# blip.net
KiCad netlist of a schematic drawn in EAGLE
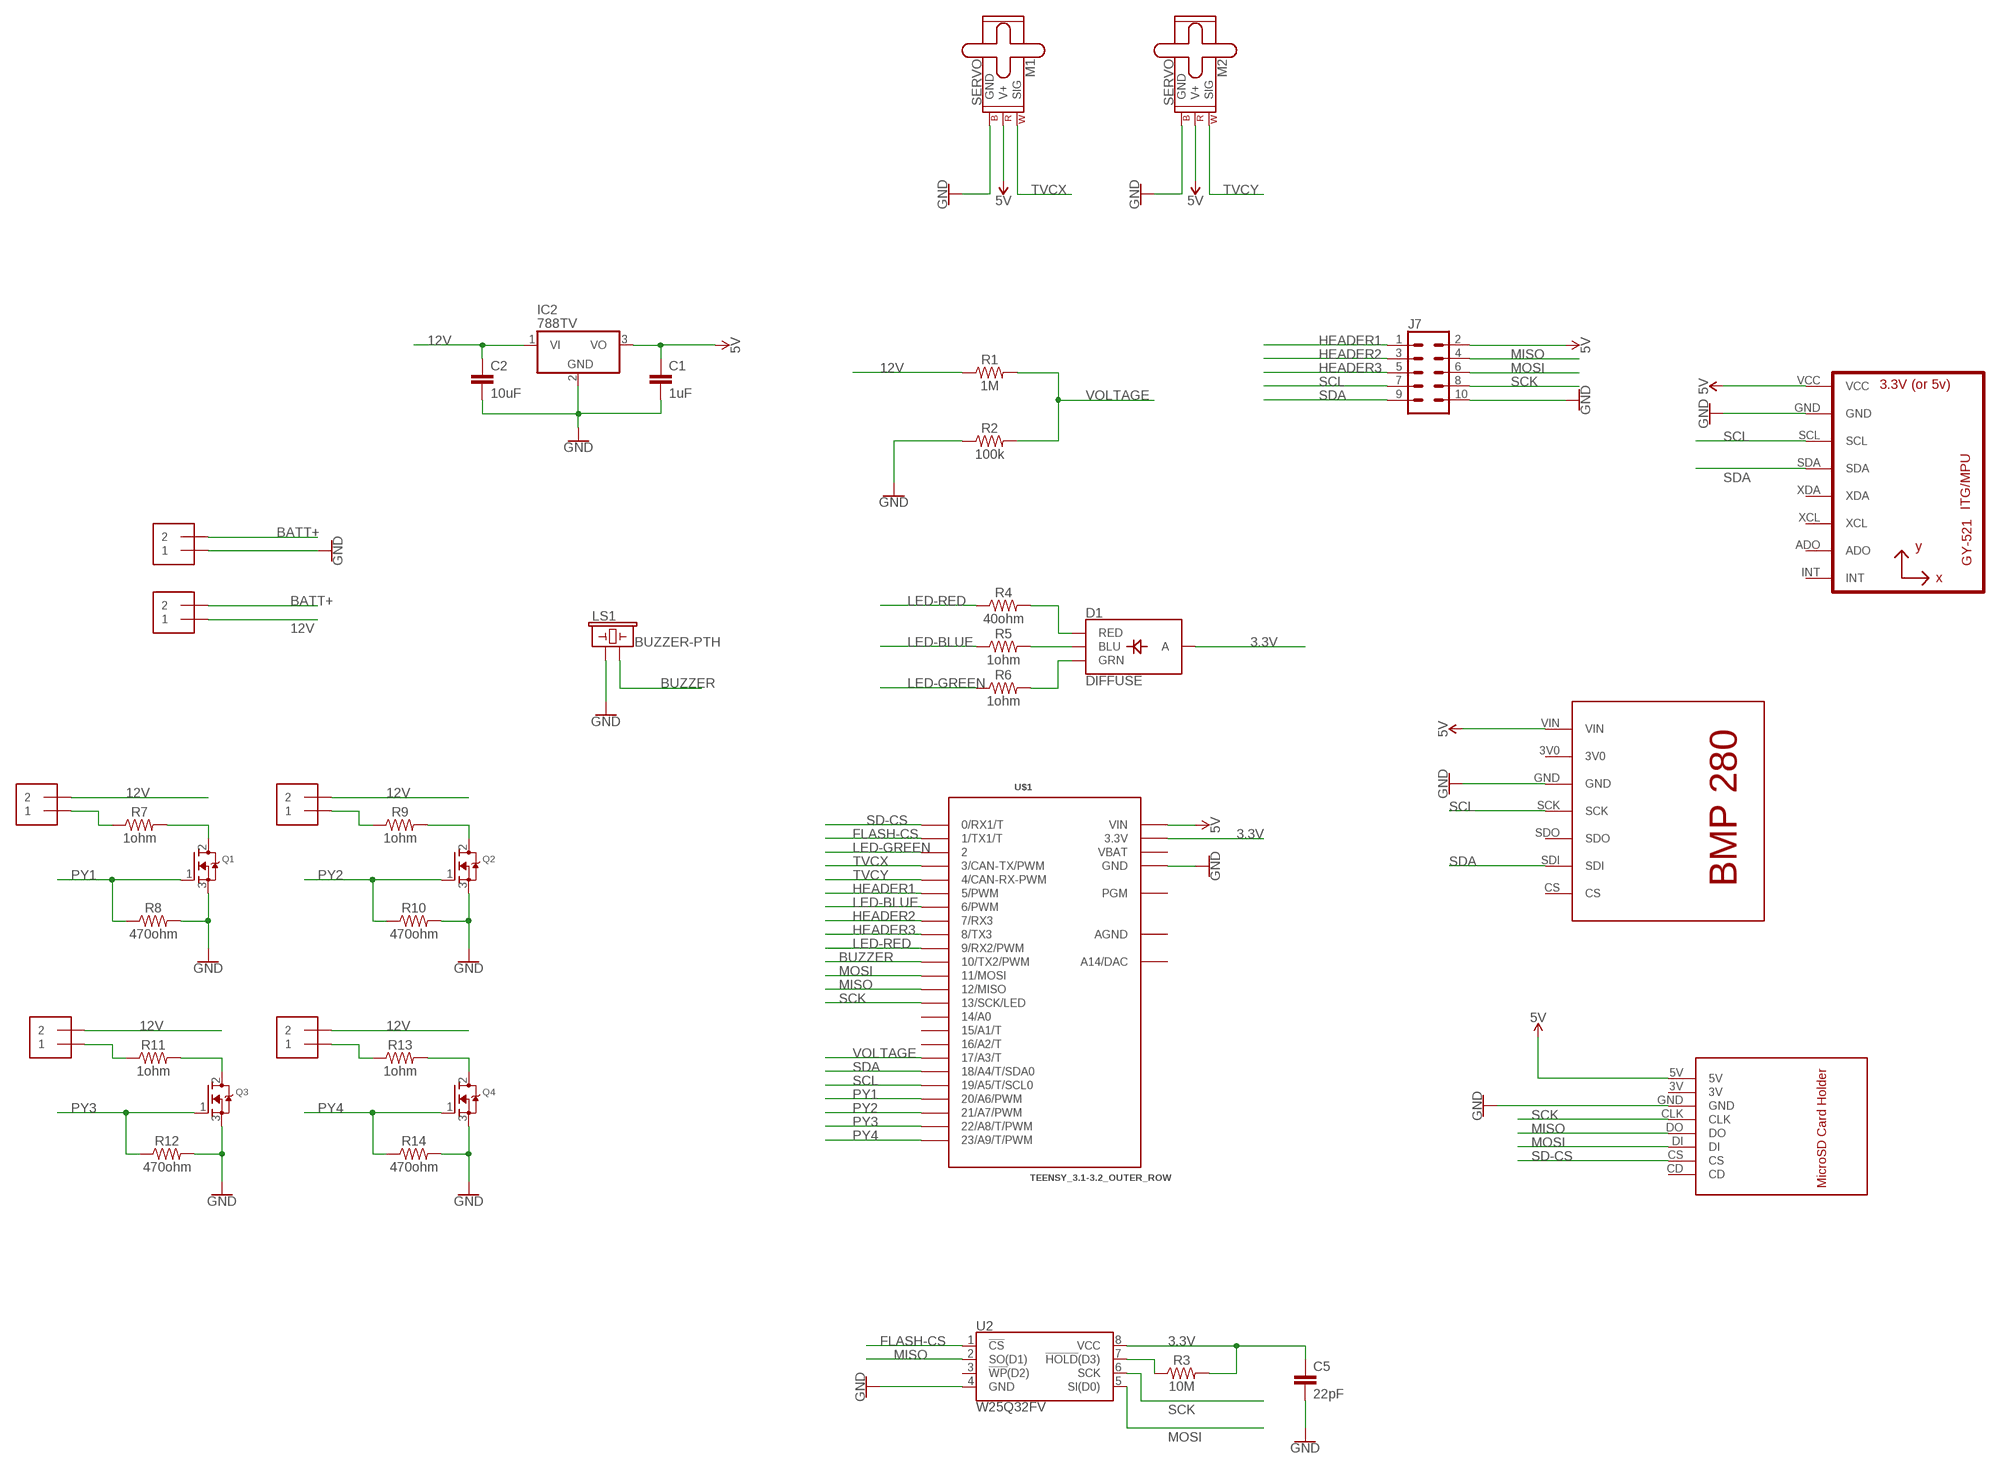
[diagram p0: schematic, sheet 1]

(export (version "E")
  (design (tool "Eeschema 10.0.6"))
  (components
    (comp (ref "C1")
      (value "1uF")
      (footprint "eagle-import:CAP-PTH-2.54")
      (libsource (lib "eagle-import") (part "22PF-PTH-2.54MM-200V-5%"))
    )
    (comp (ref "C2")
      (value "10uF")
      (footprint "eagle-import:CAP-PTH-2.54")
      (libsource (lib "eagle-import") (part "22PF-PTH-2.54MM-200V-5%"))
    )
    (comp (ref "C5")
      (value "22pF")
      (footprint "eagle-import:CAP-PTH-2.54")
      (libsource (lib "eagle-import") (part "22PF-PTH-2.54MM-200V-5%"))
    )
    (comp (ref "D1")
      (value "DIFFUSE")
      (footprint "eagle-import:LED-RGB-THRU")
      (libsource (lib "eagle-import") (part "LED-RGB-CADIFFUSE"))
    )
    (comp (ref "IC2")
      (value "788TV")
      (footprint "eagle-import:TO220V")
      (libsource (lib "eagle-import") (part "78TV8"))
    )
    (comp (ref "J1")
      (value "1X2-3.5MM")
      (footprint "eagle-import:1X2-3.5MM")
      (libsource (lib "eagle-import") (part "1X2-3.5MM"))
    )
    (comp (ref "J2")
      (value "1X2-3.5MM")
      (footprint "eagle-import:1X2-3.5MM")
      (libsource (lib "eagle-import") (part "1X2-3.5MM"))
    )
    (comp (ref "J3")
      (value "1X2-3.5MM")
      (footprint "eagle-import:1X2-3.5MM")
      (libsource (lib "eagle-import") (part "1X2-3.5MM"))
    )
    (comp (ref "J4")
      (value "1X2-3.5MM")
      (footprint "eagle-import:1X2-3.5MM")
      (libsource (lib "eagle-import") (part "1X2-3.5MM"))
    )
    (comp (ref "J5")
      (value "1X2-3.5MM")
      (footprint "eagle-import:1X2-3.5MM")
      (libsource (lib "eagle-import") (part "1X2-3.5MM"))
    )
    (comp (ref "J6")
      (value "1X2-3.5MM")
      (footprint "eagle-import:1X2-3.5MM")
      (libsource (lib "eagle-import") (part "1X2-3.5MM"))
    )
    (comp (ref "J7")
      (value "CONN_05X2NO_SILK")
      (footprint "eagle-import:2X5_NOSILK")
      (libsource (lib "eagle-import") (part "CONN_05X2NO_SILK"))
    )
    (comp (ref "LS1")
      (value "BUZZER-PTH")
      (footprint "eagle-import:BUZZER-12MM")
      (libsource (lib "eagle-import") (part "BUZZER-PTH"))
    )
    (comp (ref "M1")
      (value "SERVO")
      (footprint "eagle-import:1X03")
      (libsource (lib "eagle-import") (part "SERVO"))
    )
    (comp (ref "M2")
      (value "SERVO")
      (footprint "eagle-import:1X03")
      (libsource (lib "eagle-import") (part "SERVO"))
    )
    (comp (ref "Q1")
      (value "MOSFET-NGDS_TO220V")
      (footprint "eagle-import:TO220V")
      (libsource (lib "eagle-import") (part "MOSFET-NGDS_TO220V"))
    )
    (comp (ref "Q2")
      (value "MOSFET-NGDS_TO220V")
      (footprint "eagle-import:TO220V")
      (libsource (lib "eagle-import") (part "MOSFET-NGDS_TO220V"))
    )
    (comp (ref "Q3")
      (value "MOSFET-NGDS_TO220V")
      (footprint "eagle-import:TO220V")
      (libsource (lib "eagle-import") (part "MOSFET-NGDS_TO220V"))
    )
    (comp (ref "Q4")
      (value "MOSFET-NGDS_TO220V")
      (footprint "eagle-import:TO220V")
      (libsource (lib "eagle-import") (part "MOSFET-NGDS_TO220V"))
    )
    (comp (ref "R1")
      (value "1M")
      (footprint "eagle-import:AXIAL-0.3")
      (libsource (lib "eagle-import") (part "10MOHM-HORIZ-1/4W-5%"))
    )
    (comp (ref "R2")
      (value "100k")
      (footprint "eagle-import:AXIAL-0.3")
      (libsource (lib "eagle-import") (part "10MOHM-HORIZ-1/4W-5%"))
    )
    (comp (ref "R3")
      (value "10M")
      (footprint "eagle-import:AXIAL-0.3")
      (libsource (lib "eagle-import") (part "10MOHM-HORIZ-1/4W-5%"))
    )
    (comp (ref "R4")
      (value "40ohm")
      (footprint "eagle-import:AXIAL-0.3")
      (libsource (lib "eagle-import") (part "10MOHM-HORIZ-1/4W-5%"))
    )
    (comp (ref "R5")
      (value "1ohm")
      (footprint "eagle-import:AXIAL-0.3")
      (libsource (lib "eagle-import") (part "10MOHM-HORIZ-1/4W-5%"))
    )
    (comp (ref "R6")
      (value "1ohm")
      (footprint "eagle-import:AXIAL-0.3")
      (libsource (lib "eagle-import") (part "10MOHM-HORIZ-1/4W-5%"))
    )
    (comp (ref "R7")
      (value "1ohm")
      (footprint "eagle-import:AXIAL-0.3")
      (libsource (lib "eagle-import") (part "10MOHM-HORIZ-1/4W-5%"))
    )
    (comp (ref "R8")
      (value "470ohm")
      (footprint "eagle-import:AXIAL-0.3")
      (libsource (lib "eagle-import") (part "10MOHM-HORIZ-1/4W-5%"))
    )
    (comp (ref "R9")
      (value "1ohm")
      (footprint "eagle-import:AXIAL-0.3")
      (libsource (lib "eagle-import") (part "10MOHM-HORIZ-1/4W-5%"))
    )
    (comp (ref "R10")
      (value "470ohm")
      (footprint "eagle-import:AXIAL-0.3")
      (libsource (lib "eagle-import") (part "10MOHM-HORIZ-1/4W-5%"))
    )
    (comp (ref "R11")
      (value "1ohm")
      (footprint "eagle-import:AXIAL-0.3")
      (libsource (lib "eagle-import") (part "10MOHM-HORIZ-1/4W-5%"))
    )
    (comp (ref "R12")
      (value "470ohm")
      (footprint "eagle-import:AXIAL-0.3")
      (libsource (lib "eagle-import") (part "10MOHM-HORIZ-1/4W-5%"))
    )
    (comp (ref "R13")
      (value "1ohm")
      (footprint "eagle-import:AXIAL-0.3")
      (libsource (lib "eagle-import") (part "10MOHM-HORIZ-1/4W-5%"))
    )
    (comp (ref "R14")
      (value "470ohm")
      (footprint "eagle-import:AXIAL-0.3")
      (libsource (lib "eagle-import") (part "10MOHM-HORIZ-1/4W-5%"))
    )
    (comp (ref "U$1")
      (value "TEENSY_3.1-3.2_OUTER_ROW")
      (footprint "eagle-import:TEENSY_3.0-3.2&LC_OUTER_ROW")
      (libsource (lib "eagle-import") (part "TEENSY_3.1-3.2_OUTER_ROW"))
    )
    (comp (ref "U$2")
      (value "BMP280")
      (footprint "eagle-import:BMP280")
      (libsource (lib "eagle-import") (part "BMP280"))
    )
    (comp (ref "U$3")
      (value "SDCARD")
      (footprint "eagle-import:SDCARD")
      (libsource (lib "eagle-import") (part "SDCARD"))
    )
    (comp (ref "U1")
      (value "GY-521MPU6050")
      (footprint "eagle-import:GY-521")
      (libsource (lib "eagle-import") (part "GY-521MPU6050"))
    )
    (comp (ref "U2")
      (value "W25Q32FV")
      (footprint "eagle-import:SOIC-8")
      (libsource (lib "eagle-import") (part "W25Q32FVSS"))
    )
  )
  (nets
    (net (code "1") (name "/3.3V") (class "Default")
      (node (ref "C5") (pin "1") (pinfunction "1_1") (pintype "passive"))
      (node (ref "D1") (pin "2") (pinfunction "A_2") (pintype "bidirectional"))
      (node (ref "R3") (pin "P$2") (pinfunction "2_P$2") (pintype "passive"))
      (node (ref "U$1") (pin "3.3V") (pinfunction "3.3V_3.3V") (pintype "power_in"))
      (node (ref "U$1") (pin "3.3V1") (pinfunction "3.3V_3.3V1") (pintype "power_in"))
      (node (ref "U2") (pin "8") (pinfunction "VCC_8") (pintype "bidirectional"))
    )
    (net (code "2") (name "/12V") (class "Default")
      (node (ref "C2") (pin "1") (pinfunction "1_1") (pintype "passive"))
      (node (ref "IC2") (pin "1") (pinfunction "VI_1") (pintype "input"))
      (node (ref "J2") (pin "1") (pinfunction "1_1") (pintype "passive"))
      (node (ref "J3") (pin "2") (pinfunction "2_2") (pintype "passive"))
      (node (ref "J4") (pin "2") (pinfunction "2_2") (pintype "passive"))
      (node (ref "J5") (pin "2") (pinfunction "2_2") (pintype "passive"))
      (node (ref "J6") (pin "2") (pinfunction "2_2") (pintype "passive"))
      (node (ref "R1") (pin "P$1") (pinfunction "1_P$1") (pintype "passive"))
    )
    (net (code "3") (name "/AGND") (class "Default")
      (node (ref "U$1") (pin "AGND") (pinfunction "AGND_AGND") (pintype "power_in"))
    )
    (net (code "4") (name "/BATT+") (class "Default")
      (node (ref "J1") (pin "2") (pinfunction "2_2") (pintype "passive"))
      (node (ref "J2") (pin "2") (pinfunction "2_2") (pintype "passive"))
    )
    (net (code "5") (name "/BUZZER") (class "Default")
      (node (ref "LS1") (pin "-") (pinfunction "2_-") (pintype "passive"))
      (node (ref "U$1") (pin "10") (pinfunction "10/TX2/PWM_10") (pintype "bidirectional"))
    )
    (net (code "6") (name "/FLASH-CS") (class "Default")
      (node (ref "U$1") (pin "1") (pinfunction "1/TX1/T_1") (pintype "bidirectional"))
      (node (ref "U2") (pin "1") (pinfunction "~{CS}_1") (pintype "bidirectional"))
    )
    (net (code "7") (name "/HEADER1") (class "Default")
      (node (ref "J7") (pin "1") (pinfunction "1_1") (pintype "passive"))
      (node (ref "U$1") (pin "5") (pinfunction "5/PWM_5") (pintype "bidirectional"))
    )
    (net (code "8") (name "/HEADER2") (class "Default")
      (node (ref "J7") (pin "3") (pinfunction "3_3") (pintype "passive"))
      (node (ref "U$1") (pin "7") (pinfunction "7/RX3_7") (pintype "bidirectional"))
    )
    (net (code "9") (name "/HEADER3") (class "Default")
      (node (ref "J7") (pin "5") (pinfunction "5_5") (pintype "passive"))
      (node (ref "U$1") (pin "8") (pinfunction "8/TX3_8") (pintype "bidirectional"))
    )
    (net (code "10") (name "/LED-BLUE") (class "Default")
      (node (ref "R5") (pin "P$1") (pinfunction "1_P$1") (pintype "passive"))
      (node (ref "U$1") (pin "6") (pinfunction "6/PWM_6") (pintype "bidirectional"))
    )
    (net (code "11") (name "/LED-GREEN") (class "Default")
      (node (ref "R6") (pin "P$1") (pinfunction "1_P$1") (pintype "passive"))
      (node (ref "U$1") (pin "2") (pinfunction "2_2") (pintype "bidirectional"))
    )
    (net (code "12") (name "/LED-RED") (class "Default")
      (node (ref "R4") (pin "P$1") (pinfunction "1_P$1") (pintype "passive"))
      (node (ref "U$1") (pin "9") (pinfunction "9/RX2/PWM_9") (pintype "bidirectional"))
    )
    (net (code "13") (name "/MISO") (class "Default")
      (node (ref "J7") (pin "4") (pinfunction "4_4") (pintype "passive"))
      (node (ref "U$1") (pin "12") (pinfunction "12/MISO_12") (pintype "bidirectional"))
      (node (ref "U$3") (pin "DO") (pinfunction "DO_DO") (pintype "bidirectional"))
      (node (ref "U2") (pin "2") (pinfunction "SO(D1)_2") (pintype "bidirectional"))
    )
    (net (code "14") (name "/MOSI") (class "Default")
      (node (ref "J7") (pin "6") (pinfunction "6_6") (pintype "passive"))
      (node (ref "U$1") (pin "11") (pinfunction "11/MOSI_11") (pintype "bidirectional"))
      (node (ref "U$3") (pin "DI") (pinfunction "DI_DI") (pintype "bidirectional"))
      (node (ref "U2") (pin "5") (pinfunction "SI(D0)_5") (pintype "bidirectional"))
    )
    (net (code "15") (name "/PY1") (class "Default")
      (node (ref "Q1") (pin "1") (pinfunction "G_1") (pintype "bidirectional"))
      (node (ref "R8") (pin "P$1") (pinfunction "1_P$1") (pintype "passive"))
      (node (ref "U$1") (pin "20/A6") (pinfunction "20/A6/PWM_20/A6") (pintype "bidirectional"))
    )
    (net (code "16") (name "/PY2") (class "Default")
      (node (ref "Q2") (pin "1") (pinfunction "G_1") (pintype "bidirectional"))
      (node (ref "R10") (pin "P$1") (pinfunction "1_P$1") (pintype "passive"))
      (node (ref "U$1") (pin "21/A7") (pinfunction "21/A7/PWM_21/A7") (pintype "bidirectional"))
    )
    (net (code "17") (name "/PY3") (class "Default")
      (node (ref "Q3") (pin "1") (pinfunction "G_1") (pintype "bidirectional"))
      (node (ref "R12") (pin "P$1") (pinfunction "1_P$1") (pintype "passive"))
      (node (ref "U$1") (pin "22/A8") (pinfunction "22/A8/T/PWM_22/A8") (pintype "bidirectional"))
    )
    (net (code "18") (name "/PY4") (class "Default")
      (node (ref "Q4") (pin "1") (pinfunction "G_1") (pintype "bidirectional"))
      (node (ref "R14") (pin "P$1") (pinfunction "1_P$1") (pintype "passive"))
      (node (ref "U$1") (pin "23/A9") (pinfunction "23/A9/T/PWM_23/A9") (pintype "bidirectional"))
    )
    (net (code "19") (name "/SCK") (class "Default")
      (node (ref "J7") (pin "8") (pinfunction "8_8") (pintype "passive"))
      (node (ref "U$1") (pin "13") (pinfunction "13/SCK/LED_13") (pintype "bidirectional"))
      (node (ref "U$3") (pin "CLK") (pinfunction "CLK_CLK") (pintype "bidirectional"))
      (node (ref "U2") (pin "6") (pinfunction "SCK_6") (pintype "bidirectional"))
    )
    (net (code "20") (name "/SCL") (class "Default")
      (node (ref "J7") (pin "7") (pinfunction "7_7") (pintype "passive"))
      (node (ref "U$1") (pin "19/A5") (pinfunction "19/A5/T/SCL0_19/A5") (pintype "bidirectional"))
      (node (ref "U$2") (pin "SCK") (pinfunction "SCK_SCK") (pintype "bidirectional"))
      (node (ref "U1") (pin "SCL") (pinfunction "SCL_SCL") (pintype "bidirectional"))
    )
    (net (code "21") (name "/SD-CS") (class "Default")
      (node (ref "U$1") (pin "0") (pinfunction "0/RX1/T_0") (pintype "bidirectional"))
      (node (ref "U$3") (pin "CS") (pinfunction "CS_CS") (pintype "bidirectional"))
    )
    (net (code "22") (name "/SDA") (class "Default")
      (node (ref "J7") (pin "9") (pinfunction "9_9") (pintype "passive"))
      (node (ref "U$1") (pin "18/A4") (pinfunction "18/A4/T/SDA0_18/A4") (pintype "bidirectional"))
      (node (ref "U$2") (pin "SDI") (pinfunction "SDI_SDI") (pintype "bidirectional"))
      (node (ref "U1") (pin "SDA") (pinfunction "SDA_SDA") (pintype "bidirectional"))
    )
    (net (code "23") (name "/TVCX") (class "Default")
      (node (ref "M1") (pin "1") (pinfunction "SIG_1") (pintype "bidirectional"))
      (node (ref "U$1") (pin "3") (pinfunction "3/CAN-TX/PWM_3") (pintype "bidirectional"))
    )
    (net (code "24") (name "/TVCY") (class "Default")
      (node (ref "M2") (pin "1") (pinfunction "SIG_1") (pintype "bidirectional"))
      (node (ref "U$1") (pin "4") (pinfunction "4/CAN-RX-PWM_4") (pintype "bidirectional"))
    )
    (net (code "25") (name "/VBAT") (class "Default")
      (node (ref "U$1") (pin "VBAT") (pinfunction "VBAT_VBAT") (pintype "power_in"))
    )
    (net (code "26") (name "/VOLTAGE") (class "Default")
      (node (ref "R1") (pin "P$2") (pinfunction "2_P$2") (pintype "passive"))
      (node (ref "R2") (pin "P$2") (pinfunction "2_P$2") (pintype "passive"))
      (node (ref "U$1") (pin "17/A3") (pinfunction "17/A3/T_17/A3") (pintype "bidirectional"))
    )
    (net (code "27") (name "5V") (class "Default")
      (node (ref "C1") (pin "1") (pinfunction "1_1") (pintype "passive"))
      (node (ref "IC2") (pin "3") (pinfunction "VO_3") (pintype "passive"))
      (node (ref "J7") (pin "2") (pinfunction "2_2") (pintype "passive"))
      (node (ref "M1") (pin "2") (pinfunction "V+_2") (pintype "bidirectional"))
      (node (ref "M2") (pin "2") (pinfunction "V+_2") (pintype "bidirectional"))
      (node (ref "U$1") (pin "VIN") (pinfunction "VIN_VIN") (pintype "power_in"))
      (node (ref "U$2") (pin "VIN") (pinfunction "VIN_VIN") (pintype "bidirectional"))
      (node (ref "U$3") (pin "5V") (pinfunction "5V_5V") (pintype "bidirectional"))
      (node (ref "U1") (pin "VCC") (pinfunction "VCC_VCC") (pintype "bidirectional"))
    )
    (net (code "28") (name "GND") (class "Default")
      (node (ref "C1") (pin "2") (pinfunction "2_2") (pintype "passive"))
      (node (ref "C2") (pin "2") (pinfunction "2_2") (pintype "passive"))
      (node (ref "C5") (pin "2") (pinfunction "2_2") (pintype "passive"))
      (node (ref "IC2") (pin "2") (pinfunction "GND_2") (pintype "passive"))
      (node (ref "J1") (pin "1") (pinfunction "1_1") (pintype "passive"))
      (node (ref "J7") (pin "10") (pinfunction "10_10") (pintype "passive"))
      (node (ref "LS1") (pin "+") (pinfunction "1_+") (pintype "passive"))
      (node (ref "M1") (pin "3") (pinfunction "GND_3") (pintype "bidirectional"))
      (node (ref "M2") (pin "3") (pinfunction "GND_3") (pintype "bidirectional"))
      (node (ref "Q1") (pin "3") (pinfunction "S_3") (pintype "bidirectional"))
      (node (ref "Q2") (pin "3") (pinfunction "S_3") (pintype "bidirectional"))
      (node (ref "Q3") (pin "3") (pinfunction "S_3") (pintype "bidirectional"))
      (node (ref "Q4") (pin "3") (pinfunction "S_3") (pintype "bidirectional"))
      (node (ref "R10") (pin "P$2") (pinfunction "2_P$2") (pintype "passive"))
      (node (ref "R12") (pin "P$2") (pinfunction "2_P$2") (pintype "passive"))
      (node (ref "R14") (pin "P$2") (pinfunction "2_P$2") (pintype "passive"))
      (node (ref "R2") (pin "P$1") (pinfunction "1_P$1") (pintype "passive"))
      (node (ref "R8") (pin "P$2") (pinfunction "2_P$2") (pintype "passive"))
      (node (ref "U$1") (pin "GND") (pinfunction "GND_GND") (pintype "power_in"))
      (node (ref "U$1") (pin "GND1") (pinfunction "GND_GND1") (pintype "power_in"))
      (node (ref "U$2") (pin "GND") (pinfunction "GND_GND") (pintype "bidirectional"))
      (node (ref "U$3") (pin "GND") (pinfunction "GND_GND") (pintype "bidirectional"))
      (node (ref "U1") (pin "GND") (pinfunction "GND_GND") (pintype "bidirectional"))
      (node (ref "U2") (pin "4") (pinfunction "GND_4") (pintype "bidirectional"))
    )
    (net (code "29") (name "Net-(D1-BLU)") (class "Default")
      (node (ref "D1") (pin "4") (pinfunction "BLU_4") (pintype "bidirectional"))
      (node (ref "R5") (pin "P$2") (pinfunction "2_P$2") (pintype "passive"))
    )
    (net (code "30") (name "Net-(D1-GRN)") (class "Default")
      (node (ref "D1") (pin "3") (pinfunction "GRN_3") (pintype "bidirectional"))
      (node (ref "R6") (pin "P$2") (pinfunction "2_P$2") (pintype "passive"))
    )
    (net (code "31") (name "Net-(D1-RED)") (class "Default")
      (node (ref "D1") (pin "1") (pinfunction "RED_1") (pintype "bidirectional"))
      (node (ref "R4") (pin "P$2") (pinfunction "2_P$2") (pintype "passive"))
    )
    (net (code "32") (name "Net-(Q1-D)") (class "Default")
      (node (ref "Q1") (pin "2") (pinfunction "D_2") (pintype "bidirectional"))
      (node (ref "R7") (pin "P$2") (pinfunction "2_P$2") (pintype "passive"))
    )
    (net (code "33") (name "Net-(Q2-D)") (class "Default")
      (node (ref "Q2") (pin "2") (pinfunction "D_2") (pintype "bidirectional"))
      (node (ref "R9") (pin "P$2") (pinfunction "2_P$2") (pintype "passive"))
    )
    (net (code "34") (name "Net-(Q3-D)") (class "Default")
      (node (ref "Q3") (pin "2") (pinfunction "D_2") (pintype "bidirectional"))
      (node (ref "R11") (pin "P$2") (pinfunction "2_P$2") (pintype "passive"))
    )
    (net (code "35") (name "Net-(Q4-D)") (class "Default")
      (node (ref "Q4") (pin "2") (pinfunction "D_2") (pintype "bidirectional"))
      (node (ref "R13") (pin "P$2") (pinfunction "2_P$2") (pintype "passive"))
    )
    (net (code "36") (name "Net-(R3-1)") (class "Default")
      (node (ref "R3") (pin "P$1") (pinfunction "1_P$1") (pintype "passive"))
      (node (ref "U2") (pin "7") (pinfunction "~{HOLD}(D3)_7") (pintype "bidirectional"))
    )
    (net (code "37") (name "Net-(R7-1)") (class "Default")
      (node (ref "J3") (pin "1") (pinfunction "1_1") (pintype "passive"))
      (node (ref "R7") (pin "P$1") (pinfunction "1_P$1") (pintype "passive"))
    )
    (net (code "38") (name "Net-(R9-1)") (class "Default")
      (node (ref "J4") (pin "1") (pinfunction "1_1") (pintype "passive"))
      (node (ref "R9") (pin "P$1") (pinfunction "1_P$1") (pintype "passive"))
    )
    (net (code "39") (name "Net-(R11-1)") (class "Default")
      (node (ref "J5") (pin "1") (pinfunction "1_1") (pintype "passive"))
      (node (ref "R11") (pin "P$1") (pinfunction "1_P$1") (pintype "passive"))
    )
    (net (code "40") (name "Net-(R13-1)") (class "Default")
      (node (ref "J6") (pin "1") (pinfunction "1_1") (pintype "passive"))
      (node (ref "R13") (pin "P$1") (pinfunction "1_P$1") (pintype "passive"))
    )
    (net (code "41") (name "unconnected-(U$1-15{slash}A1{slash}T-Pad15{slash}A1)") (class "Default")
      (node (ref "U$1") (pin "15/A1") (pinfunction "15/A1/T_15/A1") (pintype "bidirectional"))
    )
    (net (code "42") (name "unconnected-(U$1-16{slash}A2{slash}T-Pad16{slash}A2)") (class "Default")
      (node (ref "U$1") (pin "16/A2") (pinfunction "16/A2/T_16/A2") (pintype "bidirectional"))
    )
    (net (code "43") (name "unconnected-(U$1-A14{slash}DAC-PadRESET{slash}DAC)") (class "Default")
      (node (ref "U$1") (pin "RESET/DAC") (pinfunction "A14/DAC_RESET/DAC") (pintype "bidirectional"))
    )
    (net (code "44") (name "unconnected-(U$1-Pad14{slash}A0)") (class "Default")
      (node (ref "U$1") (pin "14/A0") (pinfunction "14/A0_14/A0") (pintype "bidirectional"))
    )
    (net (code "45") (name "unconnected-(U$1-PadPGM)") (class "Default")
      (node (ref "U$1") (pin "PGM") (pinfunction "PGM_PGM") (pintype "bidirectional"))
    )
    (net (code "46") (name "unconnected-(U$2-Pad3V0)") (class "Default")
      (node (ref "U$2") (pin "3V0") (pinfunction "3V0_3V0") (pintype "bidirectional"))
    )
    (net (code "47") (name "unconnected-(U$2-PadCS)") (class "Default")
      (node (ref "U$2") (pin "CS") (pinfunction "CS_CS") (pintype "bidirectional"))
    )
    (net (code "48") (name "unconnected-(U$2-PadSDO)") (class "Default")
      (node (ref "U$2") (pin "SDO") (pinfunction "SDO_SDO") (pintype "bidirectional"))
    )
    (net (code "49") (name "unconnected-(U$3-Pad3V)") (class "Default")
      (node (ref "U$3") (pin "3V") (pinfunction "3V_3V") (pintype "bidirectional"))
    )
    (net (code "50") (name "unconnected-(U$3-PadCD)") (class "Default")
      (node (ref "U$3") (pin "CD") (pinfunction "CD_CD") (pintype "bidirectional"))
    )
    (net (code "51") (name "unconnected-(U1-PadADO)") (class "Default")
      (node (ref "U1") (pin "ADO") (pinfunction "ADO_ADO") (pintype "bidirectional"))
    )
    (net (code "52") (name "unconnected-(U1-PadINT)") (class "Default")
      (node (ref "U1") (pin "INT") (pinfunction "INT_INT") (pintype "bidirectional"))
    )
    (net (code "53") (name "unconnected-(U1-PadXCL)") (class "Default")
      (node (ref "U1") (pin "XCL") (pinfunction "XCL_XCL") (pintype "bidirectional"))
    )
    (net (code "54") (name "unconnected-(U1-PadXDA)") (class "Default")
      (node (ref "U1") (pin "XDA") (pinfunction "XDA_XDA") (pintype "bidirectional"))
    )
    (net (code "55") (name "unconnected-(U2-~{WP}(D2)-Pad3)") (class "Default")
      (node (ref "U2") (pin "3") (pinfunction "~{WP}(D2)_3") (pintype "bidirectional"))
    )
  )
)
